# Sheet1.net
KiCad netlist of a schematic drawn in Altium Designer
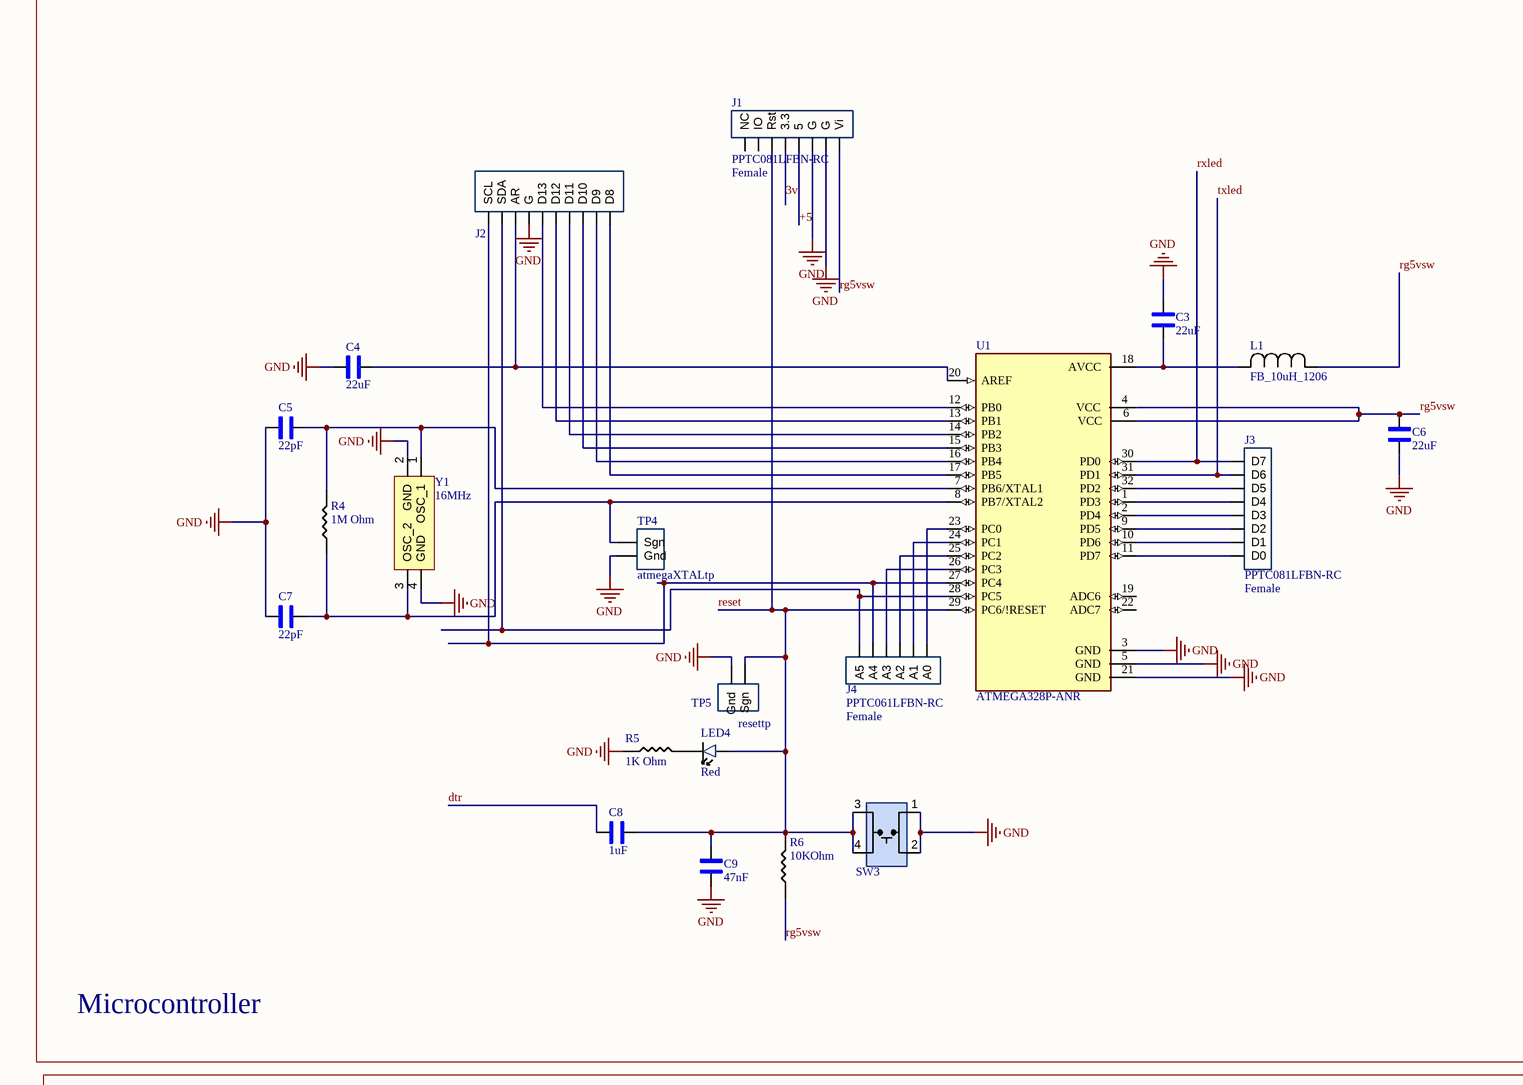
[diagram p0: Sheet1.SchDoc, top left]
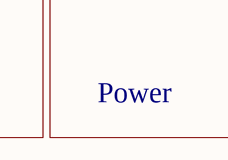
[diagram p1: Sheet1.SchDoc, top middle]
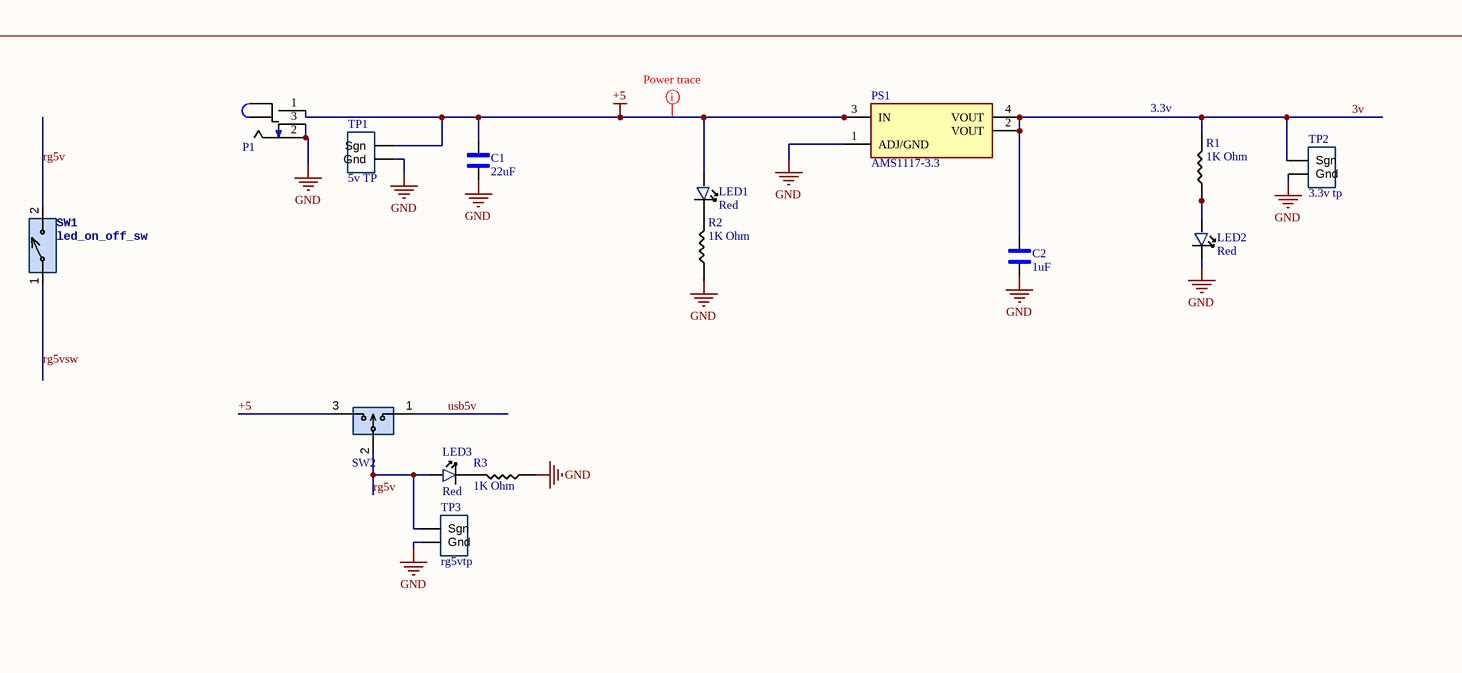
[diagram p2: Sheet1.SchDoc, top right]
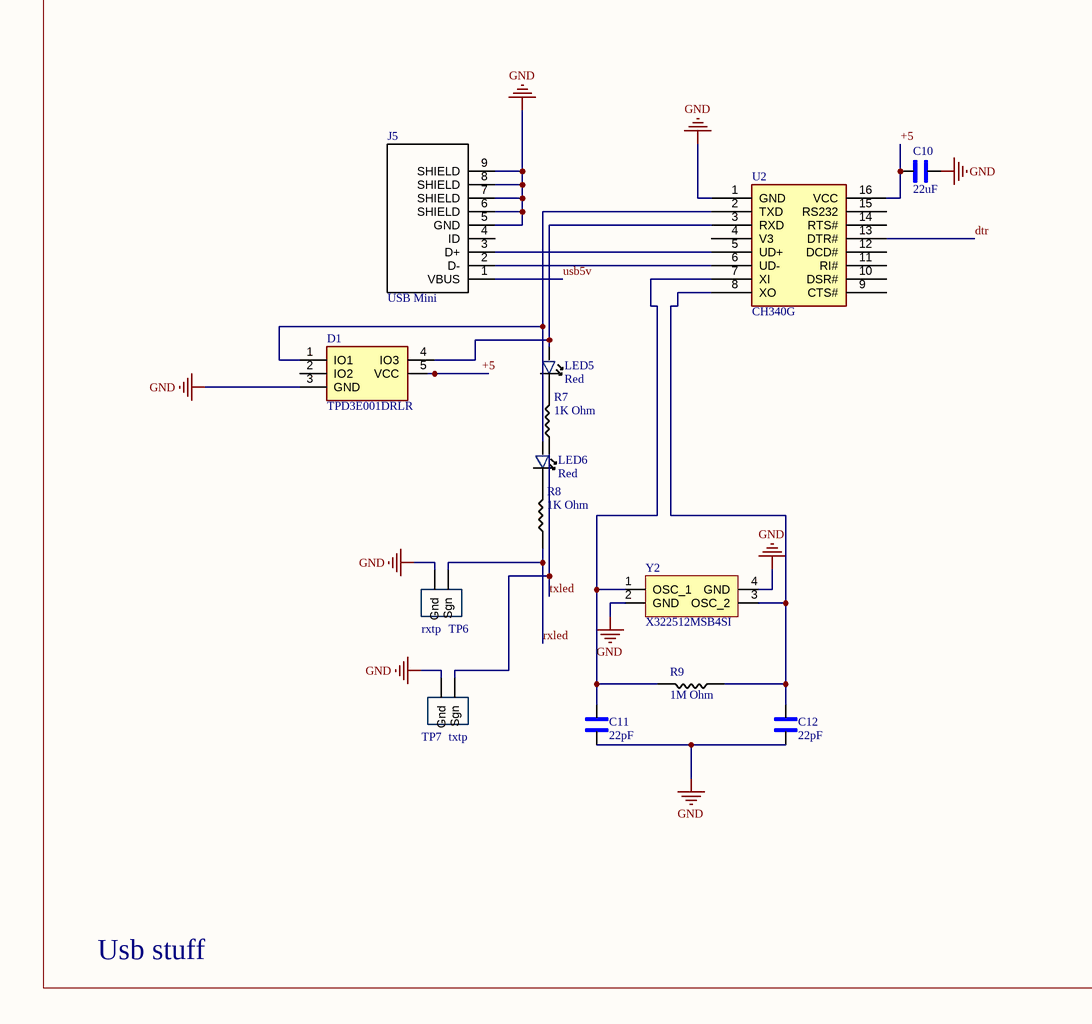
[diagram p3: Sheet1.SchDoc, bottom left]

(export (version "E")
  (design (tool "Eeschema 10.0.6"))
  (components
    (comp (ref "C1")
      (value "22uF")
      (footprint "1206_Passive_Capacitor")
      (description "22uF ±10% 25V X5R 1206 Multilayer Ceramic Capacitors MLCC - SMD/SMT RoHS")
      (fields (field (name "MFR PART #") "CL31A226KAHNNNE") (field (name "LCSC PART#") "C12891"))
      (libsource (lib "ECEN5730Lib_2023_05_DS") (part "C_22uF_1206"))
    )
    (comp (ref "C2")
      (value "1uF")
      (footprint "1206_Passive_Capacitor")
      (description "MULTILAYER CERAMIC CAPACITORS MLCC - SMD/SMT 1UF 50V 1206 ROHS")
      (fields (field (name "MFR PART #") "CL31B105KBHNNNE") (field (name "LCSC PART#") "C1848"))
      (libsource (lib "ECEN5730Lib_2023_05_DS") (part "C_1uF_1206"))
    )
    (comp (ref "C3")
      (value "22uF")
      (footprint "1206_Passive_Capacitor")
      (description "22uF ±10% 25V X5R 1206 Multilayer Ceramic Capacitors MLCC - SMD/SMT RoHS")
      (fields (field (name "MFR PART #") "CL31A226KAHNNNE") (field (name "LCSC PART#") "C12891"))
      (libsource (lib "ECEN5730Lib_2023_05_DS") (part "C_22uF_1206"))
    )
    (comp (ref "C4")
      (value "22uF")
      (footprint "1206_Passive_Capacitor")
      (description "22uF ±10% 25V X5R 1206 Multilayer Ceramic Capacitors MLCC - SMD/SMT RoHS")
      (fields (field (name "MFR PART #") "CL31A226KAHNNNE") (field (name "LCSC PART#") "C12891"))
      (libsource (lib "ECEN5730Lib_2023_05_DS") (part "C_22uF_1206"))
    )
    (comp (ref "C5")
      (value "22pF")
      (footprint "1206_Passive_Capacitor")
      (description "22pF ±5% 1kV C0G 1206 Multilayer Ceramic Capacitors MLCC - SMD/SMT RoHS")
      (fields (field (name "LCSC PART#") "C107174") (field (name "MFR PART #") "CC1206JKNPOCBN220"))
      (libsource (lib "ECEN5730Lib_2023_05_DS") (part "C_22pF_1206"))
    )
    (comp (ref "C6")
      (value "22uF")
      (footprint "1206_Passive_Capacitor")
      (description "22uF ±10% 25V X5R 1206 Multilayer Ceramic Capacitors MLCC - SMD/SMT RoHS")
      (fields (field (name "MFR PART #") "CL31A226KAHNNNE") (field (name "LCSC PART#") "C12891"))
      (libsource (lib "ECEN5730Lib_2023_05_DS") (part "C_22uF_1206"))
    )
    (comp (ref "C7")
      (value "22pF")
      (footprint "1206_Passive_Capacitor")
      (description "22pF ±5% 1kV C0G 1206 Multilayer Ceramic Capacitors MLCC - SMD/SMT RoHS")
      (fields (field (name "LCSC PART#") "C107174") (field (name "MFR PART #") "CC1206JKNPOCBN220"))
      (libsource (lib "ECEN5730Lib_2023_05_DS") (part "C_22pF_1206"))
    )
    (comp (ref "C8")
      (value "1uF")
      (footprint "1206_Passive_Capacitor")
      (description "MULTILAYER CERAMIC CAPACITORS MLCC - SMD/SMT 1UF 50V 1206 ROHS")
      (fields (field (name "MFR PART #") "CL31B105KBHNNNE") (field (name "LCSC PART#") "C1848"))
      (libsource (lib "ECEN5730Lib_2023_05_DS") (part "C_1uF_1206"))
    )
    (comp (ref "C9")
      (value "47nF")
      (footprint "1206_Passive_Capacitor")
      (description "47nF ±5% 50V C0G 1206 Multilayer Ceramic Capacitors MLCC - SMD/SMT RoHS")
      (fields (field (name "LCSC PART#") "C21812") (field (name "MFR PART #") "GRM31M5C1H473JA01L"))
      (libsource (lib "ECEN5730Lib_2023_05_DS") (part "C_47nF_1206"))
    )
    (comp (ref "C10")
      (value "22uF")
      (footprint "1206_Passive_Capacitor")
      (description "22uF ±10% 25V X5R 1206 Multilayer Ceramic Capacitors MLCC - SMD/SMT RoHS")
      (fields (field (name "MFR PART #") "CL31A226KAHNNNE") (field (name "LCSC PART#") "C12891"))
      (libsource (lib "ECEN5730Lib_2023_05_DS") (part "C_22uF_1206"))
    )
    (comp (ref "C11")
      (value "22pF")
      (footprint "1206_Passive_Capacitor")
      (description "22pF ±5% 1kV C0G 1206 Multilayer Ceramic Capacitors MLCC - SMD/SMT RoHS")
      (fields (field (name "LCSC PART#") "C107174") (field (name "MFR PART #") "CC1206JKNPOCBN220"))
      (libsource (lib "ECEN5730Lib_2023_05_DS") (part "C_22pF_1206"))
    )
    (comp (ref "C12")
      (value "22pF")
      (footprint "1206_Passive_Capacitor")
      (description "22pF ±5% 1kV C0G 1206 Multilayer Ceramic Capacitors MLCC - SMD/SMT RoHS")
      (fields (field (name "LCSC PART#") "C107174") (field (name "MFR PART #") "CC1206JKNPOCBN220"))
      (libsource (lib "ECEN5730Lib_2023_05_DS") (part "C_22pF_1206"))
    )
    (comp (ref "D1")
      (value "TPD3E001DRLR")
      (footprint "SOTFL50P160X60-5N:SOTFL50P160X60-5N")
      (description "Low-Capacitance 3-Channel +/-15KV ESD-Protection Array for High-Speed Data Interfaces")
      (fields (field (name "MOUSER PART NUMBER") "595-TPD3E001DRLR"))
      (libsource (lib "TPD3E001DRLR") (part "TPD3E001DRLR"))
    )
    (comp (ref "J1")
      (value "PPTC081LFBN-RC")
      (footprint "8_PIN_ARD-PWR_100MIL")
      (description "8 Position Header Connector 0.100\" (2.54mm) Through Hole Tin")
      (fields (field (name "LCSC PART#") "C27438") (field (name "ALTIUM_VALUE") "Female"))
      (libsource (lib "ECEN5730Lib_2023_05_DS") (part "JF_8_PIN_FEMA_ARD-Pwr"))
    )
    (comp (ref "J2")
      (value "PPTC101LFBN-RC")
      (footprint "10_PIN_ARDUINO_100MIL")
      (description "10 Position Header Connector 0.100\" (2.54mm) Through Hole Tin")
      (fields (field (name "LCSC PART#") "C225507"))
      (libsource (lib "ECEN5730Lib_2023_05_DS") (part "JF_10_PIN_FEMA_ARDUINO"))
    )
    (comp (ref "J3")
      (value "PPTC081LFBN-RC")
      (footprint "8_PIN_ARD-DIG_100MIL")
      (description "8 Position Header Connector 0.100\" (2.54mm) Through Hole Tin")
      (fields (field (name "LCSC PART#") "C27438") (field (name "ALTIUM_VALUE") "Female"))
      (libsource (lib "ECEN5730Lib_2023_05_DS") (part "JF_8_PIN_FEMA_ARD-Dig"))
    )
    (comp (ref "J4")
      (value "PPTC061LFBN-RC")
      (footprint "6_PIN_ARD-Analog_100mil")
      (description "6 Position Header Connector 0.100\" (2.54mm) Through Hole Tin")
      (fields (field (name "LCSC PART#") "C40877") (field (name "ALTIUM_VALUE") "Female"))
      (libsource (lib "ECEN5730Lib_2023_05_DS") (part "JF_6_PIN_FEMA_ARD-Anolog"))
    )
    (comp (ref "J5")
      (value "USB Mini")
      (footprint "USB_MINI_B")
      (description "Through Hole USB Connectors RoHS")
      (fields (field (name "LCSC PART#") "C46398") (field (name "MFR PART #") "920-462A2021D10102"))
      (libsource (lib "ECEN5730Lib_2023_05_DS") (part "J_USB_B_Mini"))
    )
    (comp (ref "L1")
      (value "FB_10uH_1206")
      (footprint "AIML-1206_ABR-M")
      (description "25mA 10uH ±10% 800mΩ 1206  Inductors (SMD) ROHS")
      (fields (field (name "MFR PART #") "CMI321609X100KT") (field (name "LCSC PART#") "C1051"))
      (libsource (lib "ECEN5730Lib_2023_05_DS") (part "FB_10uH_1206"))
    )
    (comp (ref "LED1")
      (value "Red")
      (footprint "LED_1206")
      (description "Red 621~631nm 1206 Light Emitting Diodes (LED) RoHS")
      (fields (field (name "MFR PART #") "15-21/R6C-FQ1R1B/2T") (field (name "LCSC PART#") "C93133"))
      (libsource (lib "ECEN5730Lib_2023_05_DS") (part "LED_RED_1206"))
    )
    (comp (ref "LED2")
      (value "Red")
      (footprint "LED_1206")
      (description "Red 621~631nm 1206 Light Emitting Diodes (LED) RoHS")
      (fields (field (name "MFR PART #") "15-21/R6C-FQ1R1B/2T") (field (name "LCSC PART#") "C93133"))
      (libsource (lib "ECEN5730Lib_2023_05_DS") (part "LED_RED_1206"))
    )
    (comp (ref "LED3")
      (value "Red")
      (footprint "LED_1206")
      (description "Red 621~631nm 1206 Light Emitting Diodes (LED) RoHS")
      (fields (field (name "MFR PART #") "15-21/R6C-FQ1R1B/2T") (field (name "LCSC PART#") "C93133"))
      (libsource (lib "ECEN5730Lib_2023_05_DS") (part "LED_RED_1206"))
    )
    (comp (ref "LED4")
      (value "Red")
      (footprint "LED_1206")
      (description "Red 621~631nm 1206 Light Emitting Diodes (LED) RoHS")
      (fields (field (name "MFR PART #") "15-21/R6C-FQ1R1B/2T") (field (name "LCSC PART#") "C93133"))
      (libsource (lib "ECEN5730Lib_2023_05_DS") (part "LED_RED_1206"))
    )
    (comp (ref "LED5")
      (value "Red")
      (footprint "LED_1206")
      (description "Red 621~631nm 1206 Light Emitting Diodes (LED) RoHS")
      (fields (field (name "MFR PART #") "15-21/R6C-FQ1R1B/2T") (field (name "LCSC PART#") "C93133"))
      (libsource (lib "ECEN5730Lib_2023_05_DS") (part "LED_RED_1206"))
    )
    (comp (ref "LED6")
      (value "Red")
      (footprint "LED_1206")
      (description "Red 621~631nm 1206 Light Emitting Diodes (LED) RoHS")
      (fields (field (name "MFR PART #") "15-21/R6C-FQ1R1B/2T") (field (name "LCSC PART#") "C93133"))
      (libsource (lib "ECEN5730Lib_2023_05_DS") (part "LED_RED_1206"))
    )
    (comp (ref "P1")
      (value "Power Jack")
      (footprint "Power_Jack")
      (description "Power Barrel Connector Jack 2.10mm ID (0.083\"), 5.50mm OD (0.217\") Through Hole, Right Angle")
      (fields (field (name "MFR PART #") "PJ-102A") (field (name "LCSC PART#") "C136744"))
      (libsource (lib "ECEN5730Lib_2023_05_DS") (part "P_Power Jack"))
    )
    (comp (ref "PS1")
      (value "AMS1117-3.3")
      (footprint "LDO")
      (description "LOW DROPOUT REGULATORS(LDO) POSITIVE FIXED 1.3V @ 800MA 15V 3.3V 1A SOT-223 ROHS")
      (fields (field (name "LCSC PART#") "C6186"))
      (libsource (lib "ECEN5730Lib_2023_05_DS") (part "PS_AMS_LDO_3v3"))
    )
    (comp (ref "R1")
      (value "1K Ohm")
      (footprint "1206_Passive_Resitor")
      (description "CHIP RESISTOR - SURFACE MOUNT 1KOHMS ±1% 1/4W 1206 ROHS")
      (fields (field (name "MFR PART #") "RNCP1206FTD1K00CT") (field (name "LCSC PART#") "C4410"))
      (libsource (lib "ECEN5730Lib_2023_05_DS") (part "R_1K_1206"))
    )
    (comp (ref "R2")
      (value "1K Ohm")
      (footprint "1206_Passive_Resitor")
      (description "CHIP RESISTOR - SURFACE MOUNT 1KOHMS ±1% 1/4W 1206 ROHS")
      (fields (field (name "MFR PART #") "RNCP1206FTD1K00CT") (field (name "LCSC PART#") "C4410"))
      (libsource (lib "ECEN5730Lib_2023_05_DS") (part "R_1K_1206"))
    )
    (comp (ref "R3")
      (value "1K Ohm")
      (footprint "1206_Passive_Resitor")
      (description "CHIP RESISTOR - SURFACE MOUNT 1KOHMS ±1% 1/4W 1206 ROHS")
      (fields (field (name "MFR PART #") "RNCP1206FTD1K00CT") (field (name "LCSC PART#") "C4410"))
      (libsource (lib "ECEN5730Lib_2023_05_DS") (part "R_1K_1206"))
    )
    (comp (ref "R4")
      (value "1M Ohm")
      (footprint "1206_Passive_Resitor")
      (description "CHIP RESISTOR - SURFACE MOUNT 1MOHMS ±1% 1/4W 1206 ROHS")
      (fields (field (name "MFR PART #") "RMCF1206JT1M00") (field (name "LCSC PART#") "C17927"))
      (libsource (lib "ECEN5730Lib_2023_05_DS") (part "R_1M_1206"))
    )
    (comp (ref "R5")
      (value "1K Ohm")
      (footprint "1206_Passive_Resitor")
      (description "CHIP RESISTOR - SURFACE MOUNT 1KOHMS ±1% 1/4W 1206 ROHS")
      (fields (field (name "MFR PART #") "RNCP1206FTD1K00CT") (field (name "LCSC PART#") "C4410"))
      (libsource (lib "ECEN5730Lib_2023_05_DS") (part "R_1K_1206"))
    )
    (comp (ref "R6")
      (value "10KOhm")
      (footprint "1206_Passive_Resitor")
      (description "10 kOhms ±5% 0.25W, 1/4W Chip Resistor 1206 (3216 Metric) Automotive AEC-Q200 Thick Film")
      (fields (field (name "MFR PART #") "RMCF1206FT10K0") (field (name "LCSC PART#") "C17902"))
      (libsource (lib "ECEN5730Lib_2023_05_DS") (part "R_10KOhm_1206"))
    )
    (comp (ref "R7")
      (value "1K Ohm")
      (footprint "1206_Passive_Resitor")
      (description "CHIP RESISTOR - SURFACE MOUNT 1KOHMS ±1% 1/4W 1206 ROHS")
      (fields (field (name "MFR PART #") "RNCP1206FTD1K00CT") (field (name "LCSC PART#") "C4410"))
      (libsource (lib "ECEN5730Lib_2023_05_DS") (part "R_1K_1206"))
    )
    (comp (ref "R8")
      (value "1K Ohm")
      (footprint "1206_Passive_Resitor")
      (description "CHIP RESISTOR - SURFACE MOUNT 1KOHMS ±1% 1/4W 1206 ROHS")
      (fields (field (name "MFR PART #") "RNCP1206FTD1K00CT") (field (name "LCSC PART#") "C4410"))
      (libsource (lib "ECEN5730Lib_2023_05_DS") (part "R_1K_1206"))
    )
    (comp (ref "R9")
      (value "1M Ohm")
      (footprint "1206_Passive_Resitor")
      (description "CHIP RESISTOR - SURFACE MOUNT 1MOHMS ±1% 1/4W 1206 ROHS")
      (fields (field (name "MFR PART #") "RMCF1206JT1M00") (field (name "LCSC PART#") "C17927"))
      (libsource (lib "ECEN5730Lib_2023_05_DS") (part "R_1M_1206"))
    )
    (comp (ref "SW1")
      (value "led_on_off_sw")
      (footprint "2Pin-Header-Conn")
      (description "2Pin Header")
      (fields (field (name "LCSC PART#") "C124375"))
      (libsource (lib "ECEN5730Lib_2023_05_DS") (part "SW_2Pin_100mil_Switch"))
    )
    (comp (ref "SW2")
      (value "PREC003SAAN-RC")
      (footprint "3_PIN_100mil")
      (description "Connector Header Through Hole 3 position 0.100\" (2.54mm)")
      (fields (field (name "LCSC PART#") "C49257"))
      (libsource (lib "ECEN5730Lib_2023_05_DS") (part "SW_3Pin_100mil_Switch"))
    )
    (comp (ref "SW3")
      (value "TL3305AF160QG")
      (footprint "Switch_JLC")
      (description "Tactile Switch SPST-NO Top Actuated Surface Mount")
      (fields (field (name "MFR PART #") "KH-4.5X4.5X4.3H-STM") (field (name "LCSC PART#") "C2837550"))
      (libsource (lib "ECEN5730Lib_2023_05_DS") (part "SW_Push_Button_JLC"))
    )
    (comp (ref "TP1")
      (value "5v TP")
      (footprint "TP10x_Probe")
      (description "Test Point 300 mil centers")
      (libsource (lib "ECEN5730Lib_2023_05_DS") (part "TP_10x_Probe"))
    )
    (comp (ref "TP2")
      (value "3.3v tp")
      (footprint "TP10x_Probe")
      (description "Test Point 300 mil centers")
      (libsource (lib "") (part "TP_10x_Probe_1"))
    )
    (comp (ref "TP3")
      (value "rg5vtp")
      (footprint "TP10x_Probe")
      (description "Test Point 300 mil centers")
      (libsource (lib "") (part "TP_10x_Probe_1"))
    )
    (comp (ref "TP4")
      (value "atmegaXTALtp")
      (footprint "TP10x_Probe")
      (description "Test Point 300 mil centers")
      (libsource (lib "") (part "TP_10x_Probe_1"))
    )
    (comp (ref "TP5")
      (value "resettp")
      (footprint "TP10x_Probe")
      (description "Test Point 300 mil centers")
      (libsource (lib "ECEN5730Lib_2023_05_DS") (part "TP_10x_Probe"))
    )
    (comp (ref "TP6")
      (value "rxtp")
      (footprint "TP10x_Probe")
      (description "Test Point 300 mil centers")
      (libsource (lib "ECEN5730Lib_2023_05_DS") (part "TP_10x_Probe"))
    )
    (comp (ref "TP7")
      (value "txtp")
      (footprint "TP10x_Probe")
      (description "Test Point 300 mil centers")
      (libsource (lib "ECEN5730Lib_2023_05_DS") (part "TP_10x_Probe"))
    )
    (comp (ref "U1")
      (value "ATMEGA328P-ANR")
      (footprint "ATMega328P")
      (description "AVR AVR® ATmega Microcontroller IC 8-Bit 20MHz 32KB (16K x 16) FLASH 32-TQFP (7x7)")
      (fields (field (name "MFR PART #") "ATMEGA328P-AU") (field (name "LCSC PART#") "C14877"))
      (libsource (lib "ECEN5730Lib_2023_05_DS") (part "U_ATMega328P"))
    )
    (comp (ref "U2")
      (value "CH340G")
      (footprint "USB to serial")
      (description "Transceiver USB 2.0 2Mbps SOP-16_150mil USB ICs RoHS")
      (fields (field (name "LCSC PART#") "C14267"))
      (libsource (lib "ECEN5730Lib_2023_05_DS") (part "U_USBtoSerial"))
    )
    (comp (ref "Y1")
      (value "16MHz")
      (footprint "Crystal resonator")
      (description "±10ppm 16000000Hz -40℃~85℃ 贴片无源晶振 60Ω 9pF SMD3225-4P Crystals ROHS")
      (fields (field (name "LCSC PART#") "C13738") (field (name "MFR PART #") "X322516MLB4SI"))
      (libsource (lib "ECEN5730Lib_2023_05_DS") (part "X_16Mhz_Res"))
    )
    (comp (ref "Y2")
      (value "X322512MSB4SI")
      (footprint "Crystal resonator")
      (description "SMD Crystal Resonators 12MHz ±10ppm SMD-3225_4P RoHS")
      (fields (field (name "LCSC PART#") "C9002"))
      (libsource (lib "ECEN5730Lib_2023_05_DS") (part "X_12MHz_Res"))
    )
  )
  (nets
    (net (code "1") (name "+5") (class "Default")
      (node (ref "C1") (pin "2") (pinfunction "2_2") (pintype "passive"))
      (node (ref "C10") (pin "1") (pinfunction "1_1") (pintype "passive"))
      (node (ref "D1") (pin "5") (pinfunction "VCC_5") (pintype "passive"))
      (node (ref "J1") (pin "5") (pinfunction "5_5") (pintype "passive"))
      (node (ref "LED1") (pin "1") (pinfunction "1_1") (pintype "passive"))
      (node (ref "P1") (pin "1") (pinfunction "1_1") (pintype "power_in"))
      (node (ref "PS1") (pin "3") (pinfunction "IN_3") (pintype "power_in"))
      (node (ref "SW2") (pin "3") (pinfunction "3_3") (pintype "passive"))
      (node (ref "TP1") (pin "1") (pinfunction "Sgn_1") (pintype "passive"))
      (node (ref "U2") (pin "16") (pinfunction "VCC_16") (pintype "passive"))
    )
    (net (code "2") (name "/3v") (class "Default")
      (node (ref "C2") (pin "2") (pinfunction "2_2") (pintype "passive"))
      (node (ref "J1") (pin "4") (pinfunction "3.3_4") (pintype "passive"))
      (node (ref "PS1") (pin "2") (pinfunction "VOUT_2") (pintype "power_in"))
      (node (ref "PS1") (pin "4") (pinfunction "VOUT_4") (pintype "power_in"))
      (node (ref "R1") (pin "2") (pinfunction "2_2") (pintype "passive"))
      (node (ref "TP2") (pin "1") (pinfunction "Sgn_1") (pintype "passive"))
    )
    (net (code "3") (name "/dtr") (class "Default")
      (node (ref "C8") (pin "1") (pinfunction "1_1") (pintype "passive"))
      (node (ref "U2") (pin "13") (pinfunction "DTR#_13") (pintype "passive"))
    )
    (net (code "4") (name "/reset") (class "Default")
      (node (ref "C8") (pin "2") (pinfunction "2_2") (pintype "passive"))
      (node (ref "C9") (pin "2") (pinfunction "2_2") (pintype "passive"))
      (node (ref "J1") (pin "3") (pinfunction "Rst_3") (pintype "passive"))
      (node (ref "LED4") (pin "1") (pinfunction "1_1") (pintype "passive"))
      (node (ref "R6") (pin "2") (pinfunction "2_2") (pintype "passive"))
      (node (ref "SW3") (pin "3") (pinfunction "3_3") (pintype "passive"))
      (node (ref "SW3") (pin "4") (pinfunction "4_4") (pintype "passive"))
      (node (ref "TP5") (pin "1") (pinfunction "Sgn_1") (pintype "passive"))
      (node (ref "U1") (pin "29") (pinfunction "PC6/!RESET_29") (pintype "bidirectional"))
    )
    (net (code "5") (name "/rg5v") (class "Default")
      (node (ref "LED3") (pin "1") (pinfunction "1_1") (pintype "passive"))
      (node (ref "SW1") (pin "2") (pinfunction "2_2") (pintype "passive"))
      (node (ref "SW2") (pin "2") (pinfunction "2_2") (pintype "passive"))
      (node (ref "TP3") (pin "1") (pinfunction "Sgn_1") (pintype "passive"))
    )
    (net (code "6") (name "/rg5vsw") (class "Default")
      (node (ref "C6") (pin "2") (pinfunction "2_2") (pintype "passive"))
      (node (ref "J1") (pin "8") (pinfunction "Vi_8") (pintype "passive"))
      (node (ref "L1") (pin "1") (pinfunction "1_1") (pintype "passive"))
      (node (ref "R6") (pin "1") (pinfunction "1_1") (pintype "passive"))
      (node (ref "SW1") (pin "1") (pinfunction "1_1") (pintype "passive"))
      (node (ref "U1") (pin "4") (pinfunction "VCC_4") (pintype "power_in"))
      (node (ref "U1") (pin "6") (pinfunction "VCC_6") (pintype "power_in"))
    )
    (net (code "7") (name "/rxled") (class "Default")
      (node (ref "J3") (pin "1") (pinfunction "D7_1") (pintype "passive"))
      (node (ref "R8") (pin "1") (pinfunction "1_1") (pintype "passive"))
      (node (ref "TP6") (pin "1") (pinfunction "Sgn_1") (pintype "passive"))
      (node (ref "U1") (pin "30") (pinfunction "PD0_30") (pintype "bidirectional"))
    )
    (net (code "8") (name "/txled") (class "Default")
      (node (ref "J3") (pin "2") (pinfunction "D6_2") (pintype "passive"))
      (node (ref "R7") (pin "1") (pinfunction "1_1") (pintype "passive"))
      (node (ref "TP7") (pin "1") (pinfunction "Sgn_1") (pintype "passive"))
      (node (ref "U1") (pin "31") (pinfunction "PD1_31") (pintype "bidirectional"))
    )
    (net (code "9") (name "/usb5v") (class "Default")
      (node (ref "J5") (pin "1") (pinfunction "VBUS_1") (pintype "passive"))
      (node (ref "SW2") (pin "1") (pinfunction "1_1") (pintype "passive"))
    )
    (net (code "10") (name "GND") (class "Default")
      (node (ref "C1") (pin "1") (pinfunction "1_1") (pintype "passive"))
      (node (ref "C10") (pin "2") (pinfunction "2_2") (pintype "passive"))
      (node (ref "C11") (pin "1") (pinfunction "1_1") (pintype "passive"))
      (node (ref "C12") (pin "1") (pinfunction "1_1") (pintype "passive"))
      (node (ref "C2") (pin "1") (pinfunction "1_1") (pintype "passive"))
      (node (ref "C3") (pin "2") (pinfunction "2_2") (pintype "passive"))
      (node (ref "C4") (pin "2") (pinfunction "2_2") (pintype "passive"))
      (node (ref "C5") (pin "1") (pinfunction "1_1") (pintype "passive"))
      (node (ref "C6") (pin "1") (pinfunction "1_1") (pintype "passive"))
      (node (ref "C7") (pin "1") (pinfunction "1_1") (pintype "passive"))
      (node (ref "C9") (pin "1") (pinfunction "1_1") (pintype "passive"))
      (node (ref "D1") (pin "3") (pinfunction "GND_3") (pintype "passive"))
      (node (ref "J1") (pin "6") (pinfunction "G_6") (pintype "passive"))
      (node (ref "J1") (pin "7") (pinfunction "G_7") (pintype "passive"))
      (node (ref "J2") (pin "4") (pinfunction "G_4") (pintype "passive"))
      (node (ref "J5") (pin "5") (pinfunction "GND_5") (pintype "passive"))
      (node (ref "J5") (pin "6") (pinfunction "SHIELD_6") (pintype "passive"))
      (node (ref "J5") (pin "7") (pinfunction "SHIELD_7") (pintype "passive"))
      (node (ref "J5") (pin "8") (pinfunction "SHIELD_8") (pintype "passive"))
      (node (ref "J5") (pin "9") (pinfunction "SHIELD_9") (pintype "passive"))
      (node (ref "LED2") (pin "2") (pinfunction "2_2") (pintype "passive"))
      (node (ref "P1") (pin "2") (pinfunction "2_2") (pintype "power_in"))
      (node (ref "P1") (pin "3") (pinfunction "3_3") (pintype "power_in"))
      (node (ref "PS1") (pin "1") (pinfunction "ADJ/GND_1") (pintype "passive"))
      (node (ref "R2") (pin "1") (pinfunction "1_1") (pintype "passive"))
      (node (ref "R3") (pin "1") (pinfunction "1_1") (pintype "passive"))
      (node (ref "R5") (pin "1") (pinfunction "1_1") (pintype "passive"))
      (node (ref "SW3") (pin "1") (pinfunction "1_1") (pintype "passive"))
      (node (ref "SW3") (pin "2") (pinfunction "2_2") (pintype "passive"))
      (node (ref "TP1") (pin "2") (pinfunction "Gnd_2") (pintype "passive"))
      (node (ref "TP2") (pin "2") (pinfunction "Gnd_2") (pintype "passive"))
      (node (ref "TP3") (pin "2") (pinfunction "Gnd_2") (pintype "passive"))
      (node (ref "TP4") (pin "2") (pinfunction "Gnd_2") (pintype "passive"))
      (node (ref "TP5") (pin "2") (pinfunction "Gnd_2") (pintype "passive"))
      (node (ref "TP6") (pin "2") (pinfunction "Gnd_2") (pintype "passive"))
      (node (ref "TP7") (pin "2") (pinfunction "Gnd_2") (pintype "passive"))
      (node (ref "U1") (pin "21") (pinfunction "GND_21") (pintype "power_in"))
      (node (ref "U1") (pin "3") (pinfunction "GND_3") (pintype "power_in"))
      (node (ref "U1") (pin "5") (pinfunction "GND_5") (pintype "power_in"))
      (node (ref "U2") (pin "1") (pinfunction "GND_1") (pintype "passive"))
      (node (ref "Y1") (pin "2") (pinfunction "GND_2") (pintype "passive"))
      (node (ref "Y1") (pin "4") (pinfunction "GND_4") (pintype "passive"))
      (node (ref "Y2") (pin "2") (pinfunction "GND_2") (pintype "passive"))
      (node (ref "Y2") (pin "4") (pinfunction "GND_4") (pintype "passive"))
    )
    (net (code "11") (name "Net-(D1-IO1)") (class "Default")
      (node (ref "D1") (pin "1") (pinfunction "IO1_1") (pintype "passive"))
      (node (ref "LED6") (pin "1") (pinfunction "1_1") (pintype "passive"))
      (node (ref "U2") (pin "2") (pinfunction "TXD_2") (pintype "passive"))
    )
    (net (code "12") (name "Net-(D1-IO3)") (class "Default")
      (node (ref "D1") (pin "4") (pinfunction "IO3_4") (pintype "passive"))
      (node (ref "LED5") (pin "1") (pinfunction "1_1") (pintype "passive"))
      (node (ref "U2") (pin "3") (pinfunction "RXD_3") (pintype "passive"))
    )
    (net (code "13") (name "Net-(J2-AR)") (class "Default")
      (node (ref "C4") (pin "1") (pinfunction "1_1") (pintype "passive"))
      (node (ref "J2") (pin "3") (pinfunction "AR_3") (pintype "passive"))
      (node (ref "U1") (pin "20") (pinfunction "AREF_20") (pintype "input"))
    )
    (net (code "14") (name "Net-(J2-D8)") (class "Default")
      (node (ref "J2") (pin "10") (pinfunction "D8_10") (pintype "passive"))
      (node (ref "U1") (pin "17") (pinfunction "PB5_17") (pintype "bidirectional"))
    )
    (net (code "15") (name "Net-(J2-D9)") (class "Default")
      (node (ref "J2") (pin "9") (pinfunction "D9_9") (pintype "passive"))
      (node (ref "U1") (pin "16") (pinfunction "PB4_16") (pintype "bidirectional"))
    )
    (net (code "16") (name "Net-(J2-D10)") (class "Default")
      (node (ref "J2") (pin "8") (pinfunction "D10_8") (pintype "passive"))
      (node (ref "U1") (pin "15") (pinfunction "PB3_15") (pintype "bidirectional"))
    )
    (net (code "17") (name "Net-(J2-D11)") (class "Default")
      (node (ref "J2") (pin "7") (pinfunction "D11_7") (pintype "passive"))
      (node (ref "U1") (pin "14") (pinfunction "PB2_14") (pintype "bidirectional"))
    )
    (net (code "18") (name "Net-(J2-D12)") (class "Default")
      (node (ref "J2") (pin "6") (pinfunction "D12_6") (pintype "passive"))
      (node (ref "U1") (pin "13") (pinfunction "PB1_13") (pintype "bidirectional"))
    )
    (net (code "19") (name "Net-(J2-D13)") (class "Default")
      (node (ref "J2") (pin "5") (pinfunction "D13_5") (pintype "passive"))
      (node (ref "U1") (pin "12") (pinfunction "PB0_12") (pintype "bidirectional"))
    )
    (net (code "20") (name "Net-(J2-SCL)") (class "Default")
      (node (ref "J2") (pin "1") (pinfunction "SCL_1") (pintype "passive"))
      (node (ref "J4") (pin "5") (pinfunction "A4_5") (pintype "passive"))
      (node (ref "U1") (pin "27") (pinfunction "PC4_27") (pintype "bidirectional"))
    )
    (net (code "21") (name "Net-(J2-SDA)") (class "Default")
      (node (ref "J2") (pin "2") (pinfunction "SDA_2") (pintype "passive"))
      (node (ref "J4") (pin "6") (pinfunction "A5_6") (pintype "passive"))
      (node (ref "U1") (pin "28") (pinfunction "PC5_28") (pintype "bidirectional"))
    )
    (net (code "22") (name "Net-(J3-D0)") (class "Default")
      (node (ref "J3") (pin "8") (pinfunction "D0_8") (pintype "passive"))
      (node (ref "U1") (pin "11") (pinfunction "PD7_11") (pintype "bidirectional"))
    )
    (net (code "23") (name "Net-(J3-D1)") (class "Default")
      (node (ref "J3") (pin "7") (pinfunction "D1_7") (pintype "passive"))
      (node (ref "U1") (pin "10") (pinfunction "PD6_10") (pintype "bidirectional"))
    )
    (net (code "24") (name "Net-(J3-D2)") (class "Default")
      (node (ref "J3") (pin "6") (pinfunction "D2_6") (pintype "passive"))
      (node (ref "U1") (pin "9") (pinfunction "PD5_9") (pintype "bidirectional"))
    )
    (net (code "25") (name "Net-(J3-D3)") (class "Default")
      (node (ref "J3") (pin "5") (pinfunction "D3_5") (pintype "passive"))
      (node (ref "U1") (pin "2") (pinfunction "PD4_2") (pintype "bidirectional"))
    )
    (net (code "26") (name "Net-(J3-D4)") (class "Default")
      (node (ref "J3") (pin "4") (pinfunction "D4_4") (pintype "passive"))
      (node (ref "U1") (pin "1") (pinfunction "PD3_1") (pintype "bidirectional"))
    )
    (net (code "27") (name "Net-(J3-D5)") (class "Default")
      (node (ref "J3") (pin "3") (pinfunction "D5_3") (pintype "passive"))
      (node (ref "U1") (pin "32") (pinfunction "PD2_32") (pintype "bidirectional"))
    )
    (net (code "28") (name "Net-(J4-A0)") (class "Default")
      (node (ref "J4") (pin "1") (pinfunction "A0_1") (pintype "passive"))
      (node (ref "U1") (pin "23") (pinfunction "PC0_23") (pintype "bidirectional"))
    )
    (net (code "29") (name "Net-(J4-A1)") (class "Default")
      (node (ref "J4") (pin "2") (pinfunction "A1_2") (pintype "passive"))
      (node (ref "U1") (pin "24") (pinfunction "PC1_24") (pintype "bidirectional"))
    )
    (net (code "30") (name "Net-(J4-A2)") (class "Default")
      (node (ref "J4") (pin "3") (pinfunction "A2_3") (pintype "passive"))
      (node (ref "U1") (pin "25") (pinfunction "PC2_25") (pintype "bidirectional"))
    )
    (net (code "31") (name "Net-(J4-A3)") (class "Default")
      (node (ref "J4") (pin "4") (pinfunction "A3_4") (pintype "passive"))
      (node (ref "U1") (pin "26") (pinfunction "PC3_26") (pintype "bidirectional"))
    )
    (net (code "32") (name "Net-(J5-D+)") (class "Default")
      (node (ref "J5") (pin "3") (pinfunction "D+_3") (pintype "passive"))
      (node (ref "U2") (pin "5") (pinfunction "UD+_5") (pintype "passive"))
    )
    (net (code "33") (name "Net-(J5-D-)") (class "Default")
      (node (ref "J5") (pin "2") (pinfunction "D-_2") (pintype "passive"))
      (node (ref "U2") (pin "6") (pinfunction "UD-_6") (pintype "passive"))
    )
    (net (code "34") (name "Net-(LED1-Pad2)") (class "Default")
      (node (ref "LED1") (pin "2") (pinfunction "2_2") (pintype "passive"))
      (node (ref "R2") (pin "2") (pinfunction "2_2") (pintype "passive"))
    )
    (net (code "35") (name "Net-(LED2-Pad1)") (class "Default")
      (node (ref "LED2") (pin "1") (pinfunction "1_1") (pintype "passive"))
      (node (ref "R1") (pin "1") (pinfunction "1_1") (pintype "passive"))
    )
    (net (code "36") (name "Net-(LED3-Pad2)") (class "Default")
      (node (ref "LED3") (pin "2") (pinfunction "2_2") (pintype "passive"))
      (node (ref "R3") (pin "2") (pinfunction "2_2") (pintype "passive"))
    )
    (net (code "37") (name "Net-(LED4-Pad2)") (class "Default")
      (node (ref "LED4") (pin "2") (pinfunction "2_2") (pintype "passive"))
      (node (ref "R5") (pin "2") (pinfunction "2_2") (pintype "passive"))
    )
    (net (code "38") (name "Net-(LED5-Pad2)") (class "Default")
      (node (ref "LED5") (pin "2") (pinfunction "2_2") (pintype "passive"))
      (node (ref "R7") (pin "2") (pinfunction "2_2") (pintype "passive"))
    )
    (net (code "39") (name "Net-(LED6-Pad2)") (class "Default")
      (node (ref "LED6") (pin "2") (pinfunction "2_2") (pintype "passive"))
      (node (ref "R8") (pin "2") (pinfunction "2_2") (pintype "passive"))
    )
    (net (code "40") (name "Net-(TP4-Sgn)") (class "Default")
      (node (ref "C7") (pin "2") (pinfunction "2_2") (pintype "passive"))
      (node (ref "R4") (pin "1") (pinfunction "1_1") (pintype "passive"))
      (node (ref "TP4") (pin "1") (pinfunction "Sgn_1") (pintype "passive"))
      (node (ref "U1") (pin "8") (pinfunction "PB7/XTAL2_8") (pintype "bidirectional"))
      (node (ref "Y1") (pin "3") (pinfunction "OSC_2_3") (pintype "passive"))
    )
    (net (code "41") (name "Net-(U1-AVCC)") (class "Default")
      (node (ref "C3") (pin "1") (pinfunction "1_1") (pintype "passive"))
      (node (ref "L1") (pin "2") (pinfunction "2_2") (pintype "passive"))
      (node (ref "U1") (pin "18") (pinfunction "AVCC_18") (pintype "power_in"))
    )
    (net (code "42") (name "Net-(U1-PB6{slash}XTAL1)") (class "Default")
      (node (ref "C5") (pin "2") (pinfunction "2_2") (pintype "passive"))
      (node (ref "R4") (pin "2") (pinfunction "2_2") (pintype "passive"))
      (node (ref "U1") (pin "7") (pinfunction "PB6/XTAL1_7") (pintype "bidirectional"))
      (node (ref "Y1") (pin "1") (pinfunction "OSC_1_1") (pintype "passive"))
    )
    (net (code "43") (name "Net-(U2-XI)") (class "Default")
      (node (ref "C11") (pin "2") (pinfunction "2_2") (pintype "passive"))
      (node (ref "R9") (pin "2") (pinfunction "2_2") (pintype "passive"))
      (node (ref "U2") (pin "7") (pinfunction "XI_7") (pintype "passive"))
      (node (ref "Y2") (pin "1") (pinfunction "OSC_1_1") (pintype "passive"))
    )
    (net (code "44") (name "Net-(U2-XO)") (class "Default")
      (node (ref "C12") (pin "2") (pinfunction "2_2") (pintype "passive"))
      (node (ref "R9") (pin "1") (pinfunction "1_1") (pintype "passive"))
      (node (ref "U2") (pin "8") (pinfunction "XO_8") (pintype "passive"))
      (node (ref "Y2") (pin "3") (pinfunction "OSC_2_3") (pintype "passive"))
    )
    (net (code "45") (name "unconnected-(D1-IO2-Pad2)") (class "Default")
      (node (ref "D1") (pin "2") (pinfunction "IO2_2") (pintype "passive"))
    )
    (net (code "46") (name "unconnected-(J1-IO-Pad2)") (class "Default")
      (node (ref "J1") (pin "2") (pinfunction "IO_2") (pintype "passive"))
    )
    (net (code "47") (name "unconnected-(J1-NC-Pad1)") (class "Default")
      (node (ref "J1") (pin "1") (pinfunction "NC_1") (pintype "passive"))
    )
    (net (code "48") (name "unconnected-(J5-ID-Pad4)") (class "Default")
      (node (ref "J5") (pin "4") (pinfunction "ID_4") (pintype "passive"))
    )
    (net (code "49") (name "unconnected-(U1-ADC6-Pad19)") (class "Default")
      (node (ref "U1") (pin "19") (pinfunction "ADC6_19") (pintype "bidirectional"))
    )
    (net (code "50") (name "unconnected-(U1-ADC7-Pad22)") (class "Default")
      (node (ref "U1") (pin "22") (pinfunction "ADC7_22") (pintype "bidirectional"))
    )
    (net (code "51") (name "unconnected-(U2-CTS#-Pad9)") (class "Default")
      (node (ref "U2") (pin "9") (pinfunction "CTS#_9") (pintype "passive"))
    )
    (net (code "52") (name "unconnected-(U2-DCD#-Pad12)") (class "Default")
      (node (ref "U2") (pin "12") (pinfunction "DCD#_12") (pintype "passive"))
    )
    (net (code "53") (name "unconnected-(U2-DSR#-Pad10)") (class "Default")
      (node (ref "U2") (pin "10") (pinfunction "DSR#_10") (pintype "passive"))
    )
    (net (code "54") (name "unconnected-(U2-RI#-Pad11)") (class "Default")
      (node (ref "U2") (pin "11") (pinfunction "RI#_11") (pintype "passive"))
    )
    (net (code "55") (name "unconnected-(U2-RS232-Pad15)") (class "Default")
      (node (ref "U2") (pin "15") (pinfunction "RS232_15") (pintype "passive"))
    )
    (net (code "56") (name "unconnected-(U2-RTS#-Pad14)") (class "Default")
      (node (ref "U2") (pin "14") (pinfunction "RTS#_14") (pintype "passive"))
    )
    (net (code "57") (name "unconnected-(U2-V3-Pad4)") (class "Default")
      (node (ref "U2") (pin "4") (pinfunction "V3_4") (pintype "passive"))
    )
  )
)
